# 03_-_MAIN_BOARD.net
KiCad netlist of a schematic drawn in Altium Designer
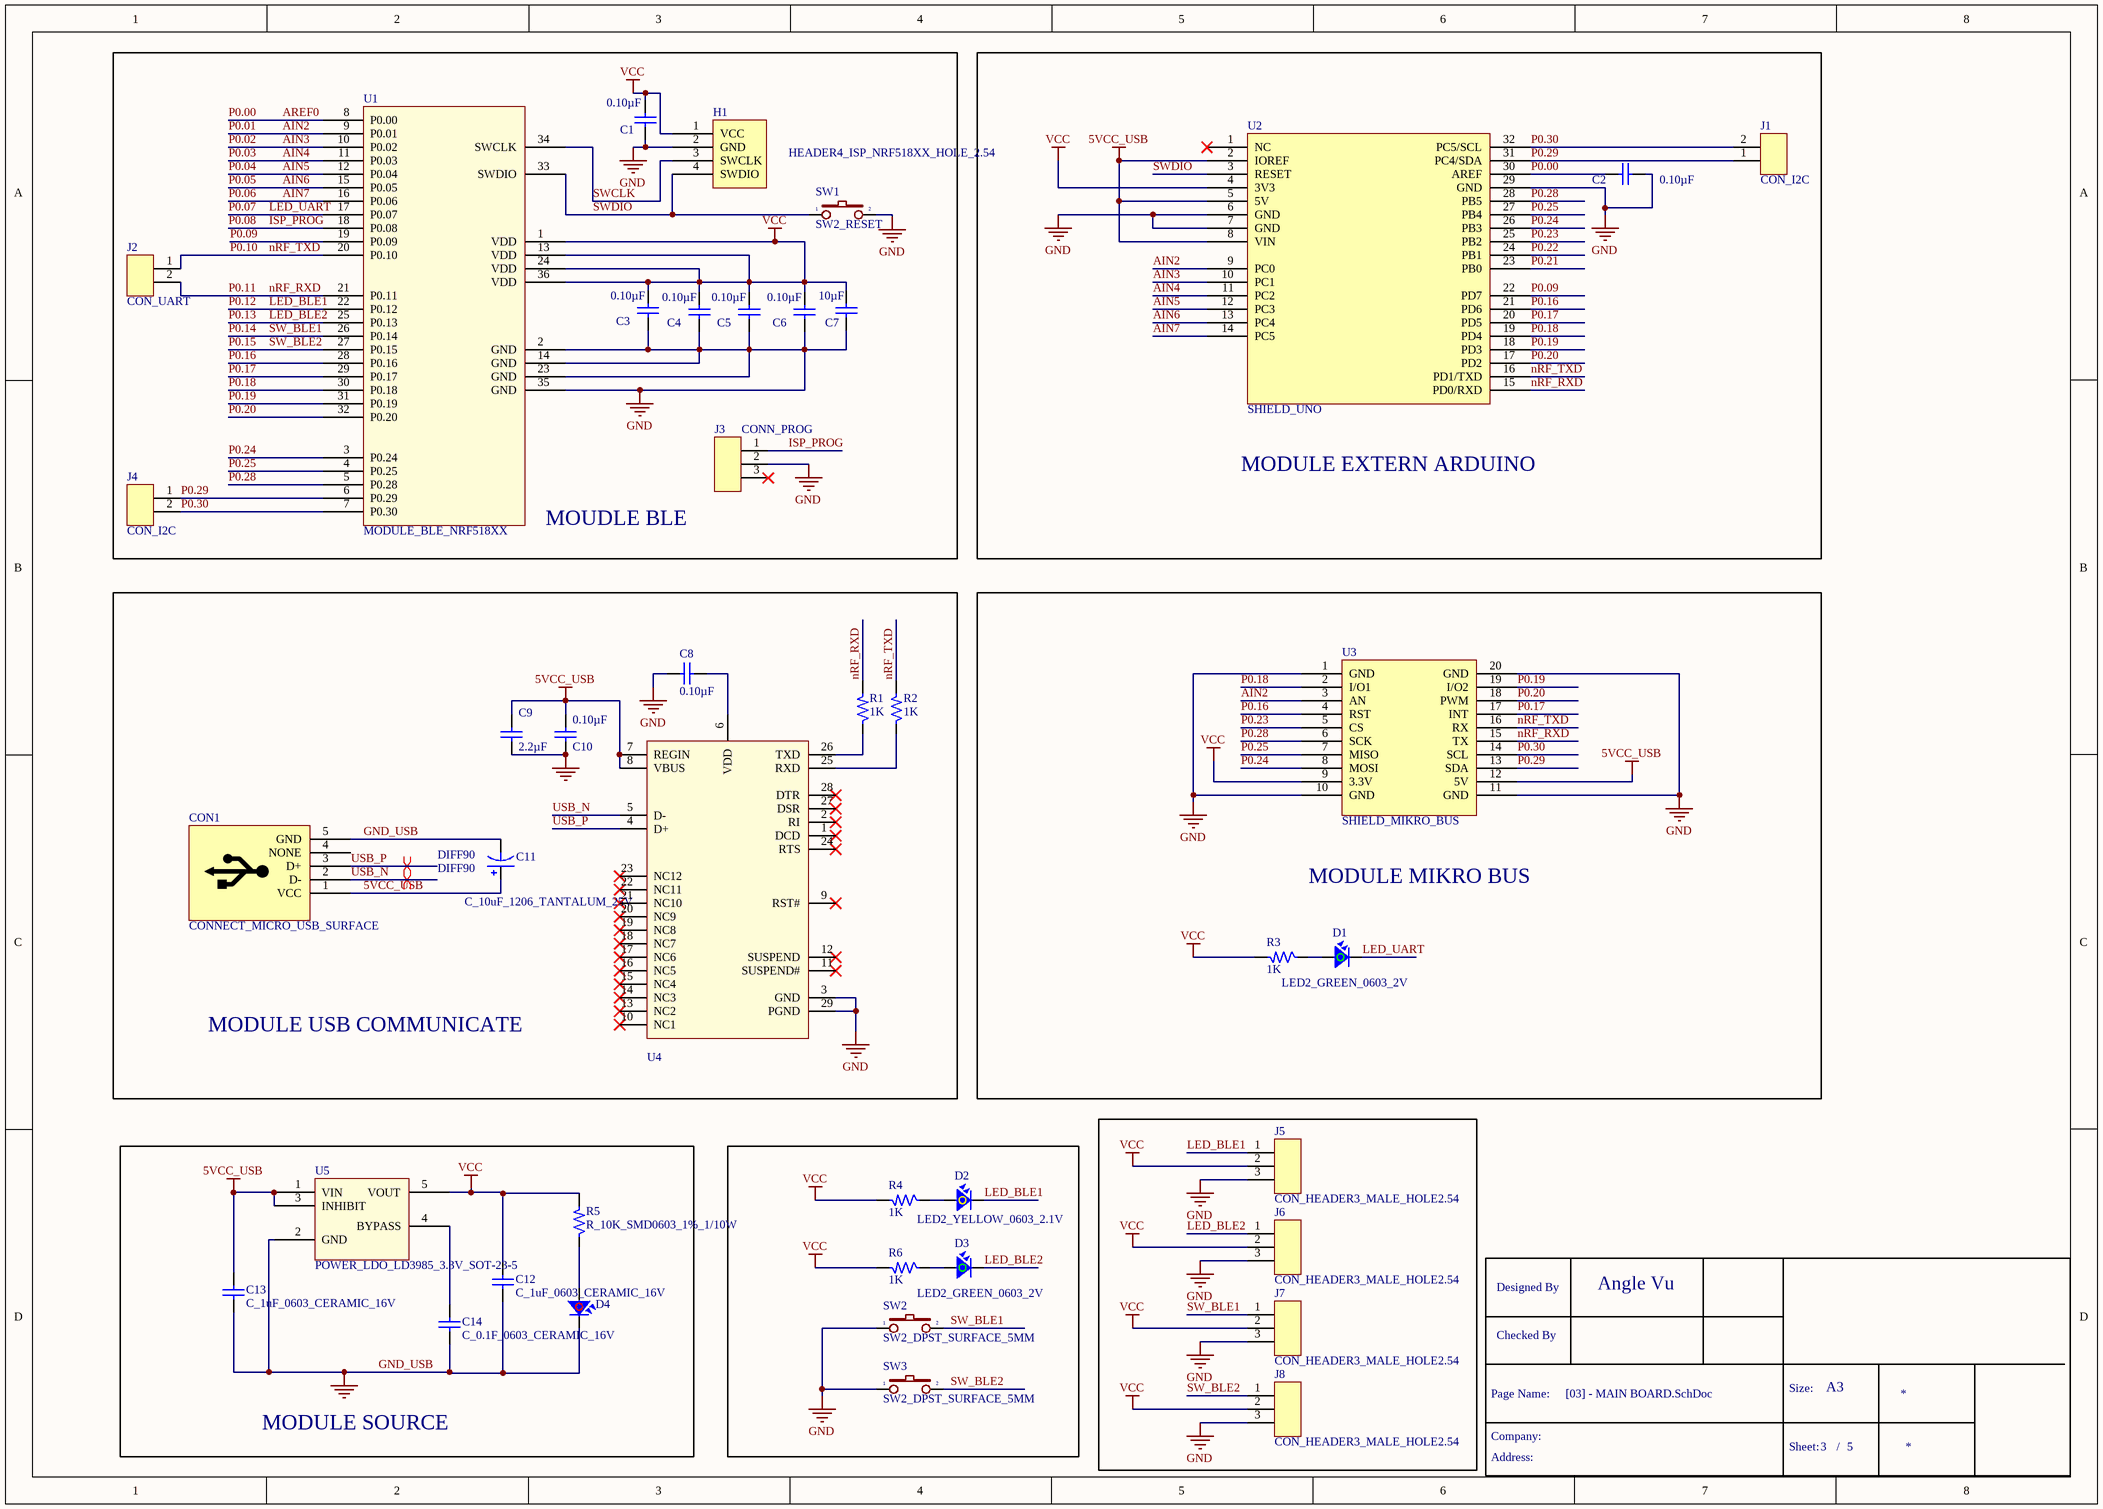
[diagram p0: [03] - MAIN BOARD.SchDoc]

(export (version "E")
  (design (tool "Eeschema 10.0.6"))
  (components
    (comp (ref "C1")
      (value "C_0.1F_0603_CERAMIC_16V")
      (footprint "CAP_SMD0603")
      (description "CAP CER 0.1UF 16V X7R 0603")
      (fields
        (field (name "MANUFACTURER") "Murata Electronics North America")
        (field (name "MANUFACTURER PART NUMBER") "GRM188R71C104KA01D")
        (field (name "CAPACITANCE") "0.10µF")
      )
      (libsource (lib "LIB_ALTIUM") (part "C_0.1F_0603_CERAMIC_16V"))
    )
    (comp (ref "C2")
      (value "C_0.1F_0603_CERAMIC_16V")
      (footprint "CAP_SMD0603")
      (description "CAP CER 0.1UF 16V X7R 0603")
      (fields
        (field (name "MANUFACTURER") "Murata Electronics North America")
        (field (name "MANUFACTURER PART NUMBER") "GRM188R71C104KA01D")
        (field (name "CAPACITANCE") "0.10µF")
      )
      (libsource (lib "LIB_ALTIUM") (part "C_0.1F_0603_CERAMIC_16V"))
    )
    (comp (ref "C3")
      (value "C_0.1F_0603_CERAMIC_16V")
      (footprint "CAP_SMD0603")
      (description "CAP CER 0.1UF 16V X7R 0603")
      (fields
        (field (name "MANUFACTURER") "Murata Electronics North America")
        (field (name "MANUFACTURER PART NUMBER") "GRM188R71C104KA01D")
        (field (name "CAPACITANCE") "0.10µF")
      )
      (libsource (lib "LIB_ALTIUM") (part "C_0.1F_0603_CERAMIC_16V"))
    )
    (comp (ref "C4")
      (value "C_0.1F_0603_CERAMIC_16V")
      (footprint "CAP_SMD0603")
      (description "CAP CER 0.1UF 16V X7R 0603")
      (fields
        (field (name "MANUFACTURER") "Murata Electronics North America")
        (field (name "MANUFACTURER PART NUMBER") "GRM188R71C104KA01D")
        (field (name "CAPACITANCE") "0.10µF")
      )
      (libsource (lib "LIB_ALTIUM") (part "C_0.1F_0603_CERAMIC_16V"))
    )
    (comp (ref "C5")
      (value "C_0.1F_0603_CERAMIC_16V")
      (footprint "CAP_SMD0603")
      (description "CAP CER 0.1UF 16V X7R 0603")
      (fields
        (field (name "MANUFACTURER") "Murata Electronics North America")
        (field (name "MANUFACTURER PART NUMBER") "GRM188R71C104KA01D")
        (field (name "CAPACITANCE") "0.10µF")
      )
      (libsource (lib "LIB_ALTIUM") (part "C_0.1F_0603_CERAMIC_16V"))
    )
    (comp (ref "C6")
      (value "C_0.1F_0603_CERAMIC_16V")
      (footprint "CAP_SMD0603")
      (description "CAP CER 0.1UF 16V X7R 0603")
      (fields
        (field (name "MANUFACTURER") "Murata Electronics North America")
        (field (name "MANUFACTURER PART NUMBER") "GRM188R71C104KA01D")
        (field (name "CAPACITANCE") "0.10µF")
      )
      (libsource (lib "LIB_ALTIUM") (part "C_0.1F_0603_CERAMIC_16V"))
    )
    (comp (ref "C7")
      (value "C_10uF_0603_CERAMIC_16V")
      (footprint "CAP_SMD0603")
      (description "CAP CER 10UF 16V X5R 0603")
      (fields
        (field (name "MANUFACTURER") "Murata Electronics North America")
        (field (name "MANUFACTURER PART NUMBER") "GRM188R61C106KAALD")
        (field (name "CAPACITANCE") "10µF")
      )
      (libsource (lib "LIB_ALTIUM") (part "C_10uF_0603_CERAMIC_16V"))
    )
    (comp (ref "C8")
      (value "C_0.1F_0603_CERAMIC_16V")
      (footprint "CAP_SMD0603")
      (description "CAP CER 0.1UF 16V X7R 0603")
      (fields
        (field (name "MANUFACTURER") "Murata Electronics North America")
        (field (name "MANUFACTURER PART NUMBER") "GRM188R71C104KA01D")
        (field (name "CAPACITANCE") "0.10µF")
      )
      (libsource (lib "LIB_ALTIUM") (part "C_0.1F_0603_CERAMIC_16V"))
    )
    (comp (ref "C9")
      (value "C_2.2uF_0603_CERAMIC_16V")
      (footprint "CAP_SMD0603")
      (description "CAP CER 2.2UF 16V X5R 0603")
      (fields
        (field (name "MANUFACTURER") "Murata Electronics North America")
        (field (name "MANUFACTURER PART NUMBER") "GRM188R61C225KE15D")
        (field (name "CAPACITANCE") "2.2µF")
      )
      (libsource (lib "LIB_ALTIUM") (part "C_2.2uF_0603_CERAMIC_16V"))
    )
    (comp (ref "C10")
      (value "C_0.1F_0603_CERAMIC_16V")
      (footprint "CAP_SMD0603")
      (description "CAP CER 0.1UF 16V X7R 0603")
      (fields
        (field (name "MANUFACTURER") "Murata Electronics North America")
        (field (name "MANUFACTURER PART NUMBER") "GRM188R71C104KA01D")
        (field (name "CAPACITANCE") "0.10µF")
      )
      (libsource (lib "LIB_ALTIUM") (part "C_0.1F_0603_CERAMIC_16V"))
    )
    (comp (ref "C11")
      (value "C_10uF_1206_TANTALUM_25V")
      (footprint "CAP_SMD1206_TANTALUM")
      (description "CAP TANT 10UF 25V 10% 1206")
      (fields
        (field (name "MANUFACTURER") "AVX Corporation")
        (field (name "MANUFACTURER PART NUMBER") "F951E106KAAAQ2")
      )
      (libsource (lib "LIB_ALTIUM") (part "C_10uF_1206_TANTALUM_25V"))
    )
    (comp (ref "C12")
      (value "C_1uF_0603_CERAMIC_16V")
      (footprint "CAP_SMD0603")
      (description "CAP CER 1UF 16V X5R 0603")
      (fields
        (field (name "MANUFACTURER") "Murata Electronics North America")
        (field (name "MANUFACTURER PART NUMBER") "GRM188R61C105KA93D")
      )
      (libsource (lib "LIB_ALTIUM") (part "C_1uF_0603_CERAMIC_16V"))
    )
    (comp (ref "C13")
      (value "C_1uF_0603_CERAMIC_16V")
      (footprint "CAP_SMD0603")
      (description "CAP CER 1UF 16V X5R 0603")
      (fields
        (field (name "MANUFACTURER") "Murata Electronics North America")
        (field (name "MANUFACTURER PART NUMBER") "GRM188R61C105KA93D")
      )
      (libsource (lib "LIB_ALTIUM") (part "C_1uF_0603_CERAMIC_16V"))
    )
    (comp (ref "C14")
      (value "C_0.1F_0603_CERAMIC_16V")
      (footprint "CAP_SMD0603")
      (description "CAP CER 0.1UF 16V X7R 0603")
      (fields
        (field (name "MANUFACTURER") "Murata Electronics North America")
        (field (name "MANUFACTURER PART NUMBER") "GRM188R71C104KA01D")
      )
      (libsource (lib "LIB_ALTIUM") (part "C_0.1F_0603_CERAMIC_16V"))
    )
    (comp (ref "CON1")
      (value "CONNECT_MICRO_USB_SURFACE")
      (footprint "CON_MICRO_USB_HOLE")
      (description "CONN RCPT STD MICRO USB TYPE B")
      (fields
        (field (name "MANUFACTURER") "Amphenol FCI")
        (field (name "MANUFACTURER PART NUMBER") "10103593-0001LF")
      )
      (libsource (lib "LIB_ALTIUM") (part "CONNECT_MICRO_USB_SURFACE"))
    )
    (comp (ref "D1")
      (value "LED2_GREEN_0603_2V")
      (footprint "LED_GREEN_SMD0603")
      (description "LED GREEN CLEAR 0603 SMD")
      (fields
        (field (name "MANUFACTURER") "Lite-On Inc.")
        (field (name "MANUFACTURER PART NUMBER") "LTST-C191KGKT")
      )
      (libsource (lib "LIB_ALTIUM") (part "LED2_GREEN_0603_2V"))
    )
    (comp (ref "D2")
      (value "LED2_YELLOW_0603_2.1V")
      (footprint "LED_YELLOW_SMD0603")
      (description "LED YELLOW CLEAR 0603 SMD")
      (fields
        (field (name "MANUFACTURER") "Lite-On Inc.")
        (field (name "MANUFACTURER PART NUMBER") "LTST-C191KSKT")
      )
      (libsource (lib "LIB_ALTIUM") (part "LED2_YELLOW_0603_2.1V"))
    )
    (comp (ref "D3")
      (value "LED2_GREEN_0603_2V")
      (footprint "LED_GREEN_SMD0603")
      (description "LED GREEN CLEAR 0603 SMD")
      (fields
        (field (name "MANUFACTURER") "Lite-On Inc.")
        (field (name "MANUFACTURER PART NUMBER") "LTST-C191KGKT")
      )
      (libsource (lib "LIB_ALTIUM") (part "LED2_GREEN_0603_2V"))
    )
    (comp (ref "D4")
      (value "LED2_RED_0603_2V")
      (footprint "LED_RED_SMD0603")
      (description "LED RED CLEAR 0603 SMD")
      (fields
        (field (name "MANUFACTURER") "Lite-On Inc.")
        (field (name "MANUFACTURER PART NUMBER") "LTST-C191KRKT")
      )
      (libsource (lib "LIB_ALTIUM") (part "LED2_RED_0603_2V"))
    )
    (comp (ref "H1")
      (value "HEADER4_ISP_NRF518XX_HOLE_2.54")
      (footprint "HEADER4_ISP_HOLE_2.54")
      (description "CONN HEADER 4POS .100 STR TIN")
      (fields
        (field (name "MANUFACTURER") "Amphenol FCI")
        (field (name "MANUFACTURER PART NUMBER") "68002-404HLF")
      )
      (libsource (lib "LIB_ALTIUM") (part "HEADER4_ISP_NRF518XX_HOLE_2.54"))
    )
    (comp (ref "J1")
      (value "CON_I2C")
      (footprint "CON_HEADER2_HOLE_2.54")
      (description "CON_HEADER10_HOLE2.54")
      (fields (field (name "MANUFACTURER") "3M") (field (name "MANUFACTURER PART NUMBER") "961102-6404-AR"))
      (libsource (lib "LIB_ALTIUM") (part "CON_HEADER2_MALE_HOLE2.54"))
    )
    (comp (ref "J2")
      (value "CON_UART")
      (footprint "CON_HEADER2_HOLE_2.54")
      (description "CON_HEADER10_HOLE2.54")
      (fields (field (name "MANUFACTURER") "3M") (field (name "MANUFACTURER PART NUMBER") "961102-6404-AR"))
      (libsource (lib "") (part "CON_HEADER2_MALE_HOLE2.54_1"))
    )
    (comp (ref "J3")
      (value "CONN_PROG")
      (footprint "CON_HEADER3_HOLE_2.54")
      (description "CON_HEADER10_HOLE2.54")
      (fields (field (name "MANUFACTURER") "3M") (field (name "MANUFACTURER PART NUMBER") "961102-6404-AR"))
      (libsource (lib "") (part "CON_HEADER3_MALE_HOLE2.54_1"))
    )
    (comp (ref "J4")
      (value "CON_I2C")
      (footprint "CON_HEADER2_HOLE_2.54")
      (description "CON_HEADER10_HOLE2.54")
      (fields (field (name "MANUFACTURER") "3M") (field (name "MANUFACTURER PART NUMBER") "961102-6404-AR"))
      (libsource (lib "") (part "CON_HEADER2_MALE_HOLE2.54_1"))
    )
    (comp (ref "J5")
      (value "CON_HEADER3_MALE_HOLE2.54")
      (footprint "CON_HEADER3_HOLE_2.54")
      (description "CON_HEADER10_HOLE2.54")
      (fields (field (name "MANUFACTURER") "3M") (field (name "MANUFACTURER PART NUMBER") "961102-6404-AR"))
      (libsource (lib "LIB_ALTIUM") (part "CON_HEADER3_MALE_HOLE2.54"))
    )
    (comp (ref "J6")
      (value "CON_HEADER3_MALE_HOLE2.54")
      (footprint "CON_HEADER3_HOLE_2.54")
      (description "CON_HEADER10_HOLE2.54")
      (fields (field (name "MANUFACTURER") "3M") (field (name "MANUFACTURER PART NUMBER") "961102-6404-AR"))
      (libsource (lib "LIB_ALTIUM") (part "CON_HEADER3_MALE_HOLE2.54"))
    )
    (comp (ref "J7")
      (value "CON_HEADER3_MALE_HOLE2.54")
      (footprint "CON_HEADER3_HOLE_2.54")
      (description "CON_HEADER10_HOLE2.54")
      (fields (field (name "MANUFACTURER") "3M") (field (name "MANUFACTURER PART NUMBER") "961102-6404-AR"))
      (libsource (lib "LIB_ALTIUM") (part "CON_HEADER3_MALE_HOLE2.54"))
    )
    (comp (ref "J8")
      (value "CON_HEADER3_MALE_HOLE2.54")
      (footprint "CON_HEADER3_HOLE_2.54")
      (description "CON_HEADER10_HOLE2.54")
      (fields (field (name "MANUFACTURER") "3M") (field (name "MANUFACTURER PART NUMBER") "961102-6404-AR"))
      (libsource (lib "LIB_ALTIUM") (part "CON_HEADER3_MALE_HOLE2.54"))
    )
    (comp (ref "R1")
      (value "R_1K2_SMD0603_1%_1/10W")
      (footprint "RES_SMD0603")
      (description "RES SMD 1.2K OHM 1% 1/10W 0603")
      (fields
        (field (name "MANUFACTURER") "Yageo")
        (field (name "MANUFACTURER PART NUMBER") "RC0603FR-071K2L")
        (field (name "RESISTANCE (OHMS)") "1K")
      )
      (libsource (lib "LIB_ALTIUM") (part "R_1K2_SMD0603_1%_1/10W"))
    )
    (comp (ref "R2")
      (value "R_1K2_SMD0603_1%_1/10W")
      (footprint "RES_SMD0603")
      (description "RES SMD 1.2K OHM 1% 1/10W 0603")
      (fields
        (field (name "MANUFACTURER") "Yageo")
        (field (name "MANUFACTURER PART NUMBER") "RC0603FR-071K2L")
        (field (name "RESISTANCE (OHMS)") "1K")
      )
      (libsource (lib "LIB_ALTIUM") (part "R_1K2_SMD0603_1%_1/10W"))
    )
    (comp (ref "R3")
      (value "R_1K2_SMD0603_1%_1/10W")
      (footprint "RES_SMD0603")
      (description "RES SMD 1.2K OHM 1% 1/10W 0603")
      (fields
        (field (name "MANUFACTURER") "Yageo")
        (field (name "MANUFACTURER PART NUMBER") "RC0603FR-071K2L")
        (field (name "RESISTANCE (OHMS)") "1K")
      )
      (libsource (lib "LIB_ALTIUM") (part "R_1K2_SMD0603_1%_1/10W"))
    )
    (comp (ref "R4")
      (value "R_1K2_SMD0603_1%_1/10W")
      (footprint "RES_SMD0603")
      (description "RES SMD 1.2K OHM 1% 1/10W 0603")
      (fields
        (field (name "MANUFACTURER") "Yageo")
        (field (name "MANUFACTURER PART NUMBER") "RC0603FR-071K2L")
        (field (name "RESISTANCE (OHMS)") "1K")
      )
      (libsource (lib "LIB_ALTIUM") (part "R_1K2_SMD0603_1%_1/10W"))
    )
    (comp (ref "R5")
      (value "R_10K_SMD0603_1%_1/10W")
      (footprint "RES_SMD0603")
      (description "RES SMD 10K OHM 1% 1/10W 0603")
      (fields
        (field (name "MANUFACTURER") "Yageo")
        (field (name "MANUFACTURER PART NUMBER") "RC0603FR-0710KL")
      )
      (libsource (lib "LIB_ALTIUM") (part "R_10K_SMD0603_1%_1/10W"))
    )
    (comp (ref "R6")
      (value "R_1K2_SMD0603_1%_1/10W")
      (footprint "RES_SMD0603")
      (description "RES SMD 1.2K OHM 1% 1/10W 0603")
      (fields
        (field (name "MANUFACTURER") "Yageo")
        (field (name "MANUFACTURER PART NUMBER") "RC0603FR-071K2L")
        (field (name "RESISTANCE (OHMS)") "1K")
      )
      (libsource (lib "LIB_ALTIUM") (part "R_1K2_SMD0603_1%_1/10W"))
    )
    (comp (ref "SW1")
      (value "SW2_RESET")
      (footprint "SW2-SMD")
      (description "SWITCH TACTILE SPST-NO 0.05A 12V")
      (fields
        (field (name "MANUFACTURER") "Wurth Electronics Inc")
        (field (name "MANUFACTURER PART NUMBER") "434121050836")
      )
      (libsource (lib "LIB_ALTIUM") (part "SW2_DPST_SURFACE_5MM"))
    )
    (comp (ref "SW2")
      (value "SW2_DPST_SURFACE_5MM")
      (footprint "SW2-SMD")
      (description "SWITCH TACTILE SPST-NO 0.05A 12V")
      (fields
        (field (name "MANUFACTURER") "Wurth Electronics Inc")
        (field (name "MANUFACTURER PART NUMBER") "434121050836")
      )
      (libsource (lib "LIB_ALTIUM") (part "SW2_DPST_SURFACE_5MM"))
    )
    (comp (ref "SW3")
      (value "SW2_DPST_SURFACE_5MM")
      (footprint "SW2-SMD")
      (description "SWITCH TACTILE SPST-NO 0.05A 12V")
      (fields
        (field (name "MANUFACTURER") "Wurth Electronics Inc")
        (field (name "MANUFACTURER PART NUMBER") "434121050836")
      )
      (libsource (lib "LIB_ALTIUM") (part "SW2_DPST_SURFACE_5MM"))
    )
    (comp (ref "U1")
      (value "MODULE_BLE_NRF518XX")
      (footprint "MODULE_NRF518xx")
      (libsource (lib "LIB_ALTIUM") (part "MODULE_BLE_NRF518XX"))
    )
    (comp (ref "U2")
      (value "SHIELD_UNO")
      (footprint "SHIELD UNO")
      (libsource (lib "LIB_ALTIUM") (part "SHIELD_UNO"))
    )
    (comp (ref "U3")
      (value "SHIELD_MIKRO_BUS")
      (footprint "SHIELD_MIKRO_BUS")
      (libsource (lib "SchematicLib") (part "SHIELD_MIKRO_BUS"))
    )
    (comp (ref "U4")
      (value "USB_CP2102-GMR")
      (footprint "QFN_28PIN_USBC2102")
      (description "IC USB-TO-UART BRIDGE 28VQFN")
      (fields
        (field (name "MANUFACTURER") "Silicon Labs")
        (field (name "MANUFACTURER PART NUMBER") "CP2102-GMR")
      )
      (libsource (lib "LIB_ALTIUM") (part "USB_CP2102-GMR"))
    )
    (comp (ref "U5")
      (value "POWER_LDO_LD3985_3.3V_SOT-23-5")
      (footprint "POWER_LDO_LDR3985-3.3")
      (description "IC REG LDO 3.3V 0.15A SOT23-5")
      (fields
        (field (name "MANUFACTURER") "STMicroelectronics")
        (field (name "MANUFACTURER PART NUMBER") "LD3985M33R")
      )
      (libsource (lib "LIB_ALTIUM") (part "POWER_LDO_LD3985_3.3V_SOT-23-5"))
    )
  )
  (nets
    (net (code "1") (name "/AIN2") (class "Default")
      (node (ref "U1") (pin "9") (pinfunction "P0.01_9") (pintype "passive"))
      (node (ref "U2") (pin "9") (pinfunction "PC0_9") (pintype "passive"))
      (node (ref "U3") (pin "3") (pinfunction "AN_3") (pintype "passive"))
    )
    (net (code "2") (name "/AIN3") (class "Default")
      (node (ref "U1") (pin "10") (pinfunction "P0.02_10") (pintype "passive"))
      (node (ref "U2") (pin "10") (pinfunction "PC1_10") (pintype "passive"))
    )
    (net (code "3") (name "/AIN4") (class "Default")
      (node (ref "U1") (pin "11") (pinfunction "P0.03_11") (pintype "passive"))
      (node (ref "U2") (pin "11") (pinfunction "PC2_11") (pintype "passive"))
    )
    (net (code "4") (name "/AIN5") (class "Default")
      (node (ref "U1") (pin "12") (pinfunction "P0.04_12") (pintype "passive"))
      (node (ref "U2") (pin "12") (pinfunction "PC3_12") (pintype "passive"))
    )
    (net (code "5") (name "/AIN6") (class "Default")
      (node (ref "U1") (pin "15") (pinfunction "P0.05_15") (pintype "passive"))
      (node (ref "U2") (pin "13") (pinfunction "PC4_13") (pintype "passive"))
    )
    (net (code "6") (name "/AIN7") (class "Default")
      (node (ref "U1") (pin "16") (pinfunction "P0.06_16") (pintype "passive"))
      (node (ref "U2") (pin "14") (pinfunction "PC5_14") (pintype "passive"))
    )
    (net (code "7") (name "/AREF0") (class "Default")
      (node (ref "C2") (pin "1") (pinfunction "1_1") (pintype "passive"))
      (node (ref "U1") (pin "8") (pinfunction "P0.00_8") (pintype "passive"))
      (node (ref "U2") (pin "30") (pinfunction "AREF_30") (pintype "passive"))
    )
    (net (code "8") (name "/ISP_PROG") (class "Default")
      (node (ref "J3") (pin "1") (pinfunction "SIGN+_1") (pintype "passive"))
      (node (ref "U1") (pin "18") (pinfunction "P0.08_18") (pintype "passive"))
    )
    (net (code "9") (name "/LED_BLE1") (class "Default")
      (node (ref "D2") (pin "2") (pinfunction "2_2") (pintype "passive"))
      (node (ref "J5") (pin "1") (pinfunction "SIGN+_1") (pintype "passive"))
      (node (ref "U1") (pin "22") (pinfunction "P0.12_22") (pintype "passive"))
    )
    (net (code "10") (name "/LED_BLE2") (class "Default")
      (node (ref "D3") (pin "2") (pinfunction "2_2") (pintype "passive"))
      (node (ref "J6") (pin "1") (pinfunction "SIGN+_1") (pintype "passive"))
      (node (ref "U1") (pin "25") (pinfunction "P0.13_25") (pintype "passive"))
    )
    (net (code "11") (name "/LED_UART") (class "Default")
      (node (ref "D1") (pin "2") (pinfunction "2_2") (pintype "passive"))
      (node (ref "U1") (pin "17") (pinfunction "P0.07_17") (pintype "passive"))
    )
    (net (code "12") (name "/P0.09") (class "Default")
      (node (ref "U1") (pin "19") (pinfunction "P0.09_19") (pintype "passive"))
      (node (ref "U2") (pin "22") (pinfunction "PD7_22") (pintype "passive"))
    )
    (net (code "13") (name "/P0.10") (class "Default")
      (node (ref "J2") (pin "1") (pinfunction "SIGN+_1") (pintype "passive"))
      (node (ref "R2") (pin "2") (pinfunction "2_2") (pintype "passive"))
      (node (ref "U1") (pin "20") (pinfunction "P0.10_20") (pintype "passive"))
      (node (ref "U2") (pin "16") (pinfunction "PD1/TXD_16") (pintype "passive"))
      (node (ref "U3") (pin "16") (pinfunction "RX_16") (pintype "passive"))
    )
    (net (code "14") (name "/P0.11") (class "Default")
      (node (ref "J2") (pin "2") (pinfunction "SIGN-_2") (pintype "passive"))
      (node (ref "R1") (pin "2") (pinfunction "2_2") (pintype "passive"))
      (node (ref "U1") (pin "21") (pinfunction "P0.11_21") (pintype "passive"))
      (node (ref "U2") (pin "15") (pinfunction "PD0/RXD_15") (pintype "passive"))
      (node (ref "U3") (pin "15") (pinfunction "TX_15") (pintype "passive"))
    )
    (net (code "15") (name "/P0.14") (class "Default")
      (node (ref "J7") (pin "1") (pinfunction "SIGN+_1") (pintype "passive"))
      (node (ref "SW2") (pin "2") (pinfunction "2_2") (pintype "passive"))
      (node (ref "U1") (pin "26") (pinfunction "P0.14_26") (pintype "passive"))
    )
    (net (code "16") (name "/P0.15") (class "Default")
      (node (ref "J8") (pin "1") (pinfunction "SIGN+_1") (pintype "passive"))
      (node (ref "SW3") (pin "2") (pinfunction "2_2") (pintype "passive"))
      (node (ref "U1") (pin "27") (pinfunction "P0.15_27") (pintype "passive"))
    )
    (net (code "17") (name "/P0.16") (class "Default")
      (node (ref "U1") (pin "28") (pinfunction "P0.16_28") (pintype "passive"))
      (node (ref "U2") (pin "21") (pinfunction "PD6_21") (pintype "passive"))
      (node (ref "U3") (pin "4") (pinfunction "RST_4") (pintype "passive"))
    )
    (net (code "18") (name "/P0.17") (class "Default")
      (node (ref "U1") (pin "29") (pinfunction "P0.17_29") (pintype "passive"))
      (node (ref "U2") (pin "20") (pinfunction "PD5_20") (pintype "passive"))
      (node (ref "U3") (pin "17") (pinfunction "INT_17") (pintype "passive"))
    )
    (net (code "19") (name "/P0.18") (class "Default")
      (node (ref "U1") (pin "30") (pinfunction "P0.18_30") (pintype "passive"))
      (node (ref "U2") (pin "19") (pinfunction "PD4_19") (pintype "passive"))
      (node (ref "U3") (pin "2") (pinfunction "I/O1_2") (pintype "passive"))
    )
    (net (code "20") (name "/P0.19") (class "Default")
      (node (ref "U1") (pin "31") (pinfunction "P0.19_31") (pintype "passive"))
      (node (ref "U2") (pin "18") (pinfunction "PD3_18") (pintype "passive"))
      (node (ref "U3") (pin "19") (pinfunction "I/O2_19") (pintype "passive"))
    )
    (net (code "21") (name "/P0.20") (class "Default")
      (node (ref "U1") (pin "32") (pinfunction "P0.20_32") (pintype "passive"))
      (node (ref "U2") (pin "17") (pinfunction "PD2_17") (pintype "passive"))
      (node (ref "U3") (pin "18") (pinfunction "PWM_18") (pintype "passive"))
    )
    (net (code "22") (name "/P0.21") (class "Default")
      (node (ref "U2") (pin "23") (pinfunction "PB0_23") (pintype "passive"))
    )
    (net (code "23") (name "/P0.22") (class "Default")
      (node (ref "U2") (pin "24") (pinfunction "PB1_24") (pintype "passive"))
    )
    (net (code "24") (name "/P0.23") (class "Default")
      (node (ref "U2") (pin "25") (pinfunction "PB2_25") (pintype "passive"))
      (node (ref "U3") (pin "5") (pinfunction "CS_5") (pintype "passive"))
    )
    (net (code "25") (name "/P0.24") (class "Default")
      (node (ref "U1") (pin "3") (pinfunction "P0.24_3") (pintype "passive"))
      (node (ref "U2") (pin "26") (pinfunction "PB3_26") (pintype "passive"))
      (node (ref "U3") (pin "8") (pinfunction "MOSI_8") (pintype "passive"))
    )
    (net (code "26") (name "/P0.25") (class "Default")
      (node (ref "U1") (pin "4") (pinfunction "P0.25_4") (pintype "passive"))
      (node (ref "U2") (pin "27") (pinfunction "PB4_27") (pintype "passive"))
      (node (ref "U3") (pin "7") (pinfunction "MISO_7") (pintype "passive"))
    )
    (net (code "27") (name "/P0.28") (class "Default")
      (node (ref "U1") (pin "5") (pinfunction "P0.28_5") (pintype "passive"))
      (node (ref "U2") (pin "28") (pinfunction "PB5_28") (pintype "passive"))
      (node (ref "U3") (pin "6") (pinfunction "SCK_6") (pintype "passive"))
    )
    (net (code "28") (name "/P0.29") (class "Default")
      (node (ref "J1") (pin "1") (pinfunction "SIGN+_1") (pintype "passive"))
      (node (ref "J4") (pin "1") (pinfunction "SIGN+_1") (pintype "passive"))
      (node (ref "U1") (pin "6") (pinfunction "P0.29_6") (pintype "passive"))
      (node (ref "U2") (pin "31") (pinfunction "PC4/SDA_31") (pintype "passive"))
      (node (ref "U3") (pin "13") (pinfunction "SDA_13") (pintype "passive"))
    )
    (net (code "29") (name "/P0.30") (class "Default")
      (node (ref "J1") (pin "2") (pinfunction "SIGN-_2") (pintype "passive"))
      (node (ref "J4") (pin "2") (pinfunction "SIGN-_2") (pintype "passive"))
      (node (ref "U1") (pin "7") (pinfunction "P0.30_7") (pintype "passive"))
      (node (ref "U2") (pin "32") (pinfunction "PC5/SCL_32") (pintype "passive"))
      (node (ref "U3") (pin "14") (pinfunction "SCL_14") (pintype "passive"))
    )
    (net (code "30") (name "/SWCLK") (class "Default")
      (node (ref "H1") (pin "3") (pinfunction "SWCLK_3") (pintype "passive"))
      (node (ref "U1") (pin "34") (pinfunction "SWCLK_34") (pintype "passive"))
    )
    (net (code "31") (name "/SWDIO") (class "Default")
      (node (ref "H1") (pin "4") (pinfunction "SWDIO_4") (pintype "passive"))
      (node (ref "SW1") (pin "1") (pinfunction "1_1") (pintype "passive"))
      (node (ref "U1") (pin "33") (pinfunction "SWDIO_33") (pintype "passive"))
      (node (ref "U2") (pin "3") (pinfunction "RESET_3") (pintype "passive"))
    )
    (net (code "32") (name "/USB_N") (class "Default")
      (node (ref "CON1") (pin "2") (pinfunction "D-_2") (pintype "passive"))
      (node (ref "U4") (pin "5") (pinfunction "D-_5") (pintype "passive"))
    )
    (net (code "33") (name "/USB_P") (class "Default")
      (node (ref "CON1") (pin "3") (pinfunction "D+_3") (pintype "passive"))
      (node (ref "U4") (pin "4") (pinfunction "D+_4") (pintype "passive"))
    )
    (net (code "34") (name "5VCC_USB") (class "Default")
      (node (ref "C10") (pin "2") (pinfunction "2_2") (pintype "passive"))
      (node (ref "C11") (pin "1") (pinfunction "1_1") (pintype "passive"))
      (node (ref "C13") (pin "2") (pinfunction "2_2") (pintype "passive"))
      (node (ref "C9") (pin "2") (pinfunction "2_2") (pintype "passive"))
      (node (ref "CON1") (pin "1") (pinfunction "VCC_1") (pintype "passive"))
      (node (ref "U2") (pin "2") (pinfunction "IOREF_2") (pintype "passive"))
      (node (ref "U2") (pin "5") (pinfunction "5V_5") (pintype "passive"))
      (node (ref "U2") (pin "8") (pinfunction "VIN_8") (pintype "passive"))
      (node (ref "U3") (pin "12") (pinfunction "5V_12") (pintype "passive"))
      (node (ref "U4") (pin "7") (pinfunction "REGIN_7") (pintype "passive"))
      (node (ref "U4") (pin "8") (pinfunction "VBUS_8") (pintype "passive"))
      (node (ref "U5") (pin "1") (pinfunction "VIN_1") (pintype "passive"))
      (node (ref "U5") (pin "3") (pinfunction "INHIBIT_3") (pintype "passive"))
    )
    (net (code "35") (name "GND") (class "Default")
      (node (ref "C1") (pin "1") (pinfunction "1_1") (pintype "passive"))
      (node (ref "C10") (pin "1") (pinfunction "1_1") (pintype "passive"))
      (node (ref "C11") (pin "2") (pinfunction "2_2") (pintype "passive"))
      (node (ref "C12") (pin "1") (pinfunction "1_1") (pintype "passive"))
      (node (ref "C13") (pin "1") (pinfunction "1_1") (pintype "passive"))
      (node (ref "C14") (pin "1") (pinfunction "1_1") (pintype "passive"))
      (node (ref "C2") (pin "2") (pinfunction "2_2") (pintype "passive"))
      (node (ref "C3") (pin "1") (pinfunction "1_1") (pintype "passive"))
      (node (ref "C4") (pin "1") (pinfunction "1_1") (pintype "passive"))
      (node (ref "C5") (pin "1") (pinfunction "1_1") (pintype "passive"))
      (node (ref "C6") (pin "1") (pinfunction "1_1") (pintype "passive"))
      (node (ref "C7") (pin "1") (pinfunction "1_1") (pintype "passive"))
      (node (ref "C8") (pin "2") (pinfunction "2_2") (pintype "passive"))
      (node (ref "C9") (pin "1") (pinfunction "1_1") (pintype "passive"))
      (node (ref "CON1") (pin "5") (pinfunction "GND_5") (pintype "passive"))
      (node (ref "D4") (pin "2") (pinfunction "2_2") (pintype "passive"))
      (node (ref "H1") (pin "2") (pinfunction "GND_2") (pintype "passive"))
      (node (ref "J3") (pin "2") (pinfunction "SIGN-_2") (pintype "passive"))
      (node (ref "J5") (pin "3") (pinfunction "3_3") (pintype "passive"))
      (node (ref "J6") (pin "3") (pinfunction "3_3") (pintype "passive"))
      (node (ref "J7") (pin "3") (pinfunction "3_3") (pintype "passive"))
      (node (ref "J8") (pin "3") (pinfunction "3_3") (pintype "passive"))
      (node (ref "SW1") (pin "2") (pinfunction "2_2") (pintype "passive"))
      (node (ref "SW2") (pin "1") (pinfunction "1_1") (pintype "passive"))
      (node (ref "SW3") (pin "1") (pinfunction "1_1") (pintype "passive"))
      (node (ref "U1") (pin "14") (pinfunction "GND_14") (pintype "passive"))
      (node (ref "U1") (pin "2") (pinfunction "GND_2") (pintype "passive"))
      (node (ref "U1") (pin "23") (pinfunction "GND_23") (pintype "passive"))
      (node (ref "U1") (pin "35") (pinfunction "GND_35") (pintype "passive"))
      (node (ref "U2") (pin "29") (pinfunction "GND_29") (pintype "passive"))
      (node (ref "U2") (pin "6") (pinfunction "GND_6") (pintype "passive"))
      (node (ref "U2") (pin "7") (pinfunction "GND_7") (pintype "passive"))
      (node (ref "U3") (pin "1") (pinfunction "GND_1") (pintype "passive"))
      (node (ref "U3") (pin "10") (pinfunction "GND_10") (pintype "passive"))
      (node (ref "U3") (pin "11") (pinfunction "GND_11") (pintype "passive"))
      (node (ref "U3") (pin "20") (pinfunction "GND_20") (pintype "passive"))
      (node (ref "U4") (pin "29") (pinfunction "PGND_29") (pintype "passive"))
      (node (ref "U4") (pin "3") (pinfunction "GND_3") (pintype "passive"))
      (node (ref "U5") (pin "2") (pinfunction "GND_2") (pintype "passive"))
    )
    (net (code "36") (name "Net-(D1-Pad1)") (class "Default")
      (node (ref "D1") (pin "1") (pinfunction "1_1") (pintype "passive"))
      (node (ref "R3") (pin "1") (pinfunction "1_1") (pintype "passive"))
    )
    (net (code "37") (name "Net-(D2-Pad1)") (class "Default")
      (node (ref "D2") (pin "1") (pinfunction "1_1") (pintype "passive"))
      (node (ref "R4") (pin "1") (pinfunction "1_1") (pintype "passive"))
    )
    (net (code "38") (name "Net-(D3-Pad1)") (class "Default")
      (node (ref "D3") (pin "1") (pinfunction "1_1") (pintype "passive"))
      (node (ref "R6") (pin "1") (pinfunction "1_1") (pintype "passive"))
    )
    (net (code "39") (name "Net-(D4-Pad1)") (class "Default")
      (node (ref "D4") (pin "1") (pinfunction "1_1") (pintype "passive"))
      (node (ref "R5") (pin "1") (pinfunction "1_1") (pintype "passive"))
    )
    (net (code "40") (name "Net-(U4-RXD)") (class "Default")
      (node (ref "R2") (pin "1") (pinfunction "1_1") (pintype "passive"))
      (node (ref "U4") (pin "25") (pinfunction "RXD_25") (pintype "passive"))
    )
    (net (code "41") (name "Net-(U4-TXD)") (class "Default")
      (node (ref "R1") (pin "1") (pinfunction "1_1") (pintype "passive"))
      (node (ref "U4") (pin "26") (pinfunction "TXD_26") (pintype "passive"))
    )
    (net (code "42") (name "Net-(U4-VDD)") (class "Default")
      (node (ref "C8") (pin "1") (pinfunction "1_1") (pintype "passive"))
      (node (ref "U4") (pin "6") (pinfunction "VDD_6") (pintype "passive"))
    )
    (net (code "43") (name "Net-(U5-BYPASS)") (class "Default")
      (node (ref "C14") (pin "2") (pinfunction "2_2") (pintype "passive"))
      (node (ref "U5") (pin "4") (pinfunction "BYPASS_4") (pintype "passive"))
    )
    (net (code "44") (name "VCC") (class "Default")
      (node (ref "C1") (pin "2") (pinfunction "2_2") (pintype "passive"))
      (node (ref "C12") (pin "2") (pinfunction "2_2") (pintype "passive"))
      (node (ref "C3") (pin "2") (pinfunction "2_2") (pintype "passive"))
      (node (ref "C4") (pin "2") (pinfunction "2_2") (pintype "passive"))
      (node (ref "C5") (pin "2") (pinfunction "2_2") (pintype "passive"))
      (node (ref "C6") (pin "2") (pinfunction "2_2") (pintype "passive"))
      (node (ref "C7") (pin "2") (pinfunction "2_2") (pintype "passive"))
      (node (ref "H1") (pin "1") (pinfunction "VCC_1") (pintype "passive"))
      (node (ref "J5") (pin "2") (pinfunction "SIGN-_2") (pintype "passive"))
      (node (ref "J6") (pin "2") (pinfunction "SIGN-_2") (pintype "passive"))
      (node (ref "J7") (pin "2") (pinfunction "SIGN-_2") (pintype "passive"))
      (node (ref "J8") (pin "2") (pinfunction "SIGN-_2") (pintype "passive"))
      (node (ref "R3") (pin "2") (pinfunction "2_2") (pintype "passive"))
      (node (ref "R4") (pin "2") (pinfunction "2_2") (pintype "passive"))
      (node (ref "R5") (pin "2") (pinfunction "2_2") (pintype "passive"))
      (node (ref "R6") (pin "2") (pinfunction "2_2") (pintype "passive"))
      (node (ref "U1") (pin "1") (pinfunction "VDD_1") (pintype "passive"))
      (node (ref "U1") (pin "13") (pinfunction "VDD_13") (pintype "passive"))
      (node (ref "U1") (pin "24") (pinfunction "VDD_24") (pintype "passive"))
      (node (ref "U1") (pin "36") (pinfunction "VDD_36") (pintype "passive"))
      (node (ref "U2") (pin "4") (pinfunction "3V3_4") (pintype "passive"))
      (node (ref "U3") (pin "9") (pinfunction "3.3V_9") (pintype "passive"))
      (node (ref "U5") (pin "5") (pinfunction "VOUT_5") (pintype "passive"))
    )
    (net (code "45") (name "unconnected-(CON1-NONE-Pad4)") (class "Default")
      (node (ref "CON1") (pin "4") (pinfunction "NONE_4") (pintype "passive"))
    )
    (net (code "46") (name "unconnected-(J3-Pad3)") (class "Default")
      (node (ref "J3") (pin "3") (pinfunction "3_3") (pintype "passive+no_connect"))
    )
    (net (code "47") (name "unconnected-(U2-NC-Pad1)") (class "Default")
      (node (ref "U2") (pin "1") (pinfunction "NC_1") (pintype "passive+no_connect"))
    )
    (net (code "48") (name "unconnected-(U4-DCD-Pad1)") (class "Default")
      (node (ref "U4") (pin "1") (pinfunction "DCD_1") (pintype "passive+no_connect"))
    )
    (net (code "49") (name "unconnected-(U4-DSR-Pad27)") (class "Default")
      (node (ref "U4") (pin "27") (pinfunction "DSR_27") (pintype "passive+no_connect"))
    )
    (net (code "50") (name "unconnected-(U4-DTR-Pad28)") (class "Default")
      (node (ref "U4") (pin "28") (pinfunction "DTR_28") (pintype "passive+no_connect"))
    )
    (net (code "51") (name "unconnected-(U4-NC1-Pad10)") (class "Default")
      (node (ref "U4") (pin "10") (pinfunction "NC1_10") (pintype "passive+no_connect"))
    )
    (net (code "52") (name "unconnected-(U4-NC2-Pad13)") (class "Default")
      (node (ref "U4") (pin "13") (pinfunction "NC2_13") (pintype "passive+no_connect"))
    )
    (net (code "53") (name "unconnected-(U4-NC3-Pad14)") (class "Default")
      (node (ref "U4") (pin "14") (pinfunction "NC3_14") (pintype "passive+no_connect"))
    )
    (net (code "54") (name "unconnected-(U4-NC4-Pad15)") (class "Default")
      (node (ref "U4") (pin "15") (pinfunction "NC4_15") (pintype "passive+no_connect"))
    )
    (net (code "55") (name "unconnected-(U4-NC5-Pad16)") (class "Default")
      (node (ref "U4") (pin "16") (pinfunction "NC5_16") (pintype "passive+no_connect"))
    )
    (net (code "56") (name "unconnected-(U4-NC6-Pad17)") (class "Default")
      (node (ref "U4") (pin "17") (pinfunction "NC6_17") (pintype "passive+no_connect"))
    )
    (net (code "57") (name "unconnected-(U4-NC7-Pad18)") (class "Default")
      (node (ref "U4") (pin "18") (pinfunction "NC7_18") (pintype "passive+no_connect"))
    )
    (net (code "58") (name "unconnected-(U4-NC8-Pad19)") (class "Default")
      (node (ref "U4") (pin "19") (pinfunction "NC8_19") (pintype "passive+no_connect"))
    )
    (net (code "59") (name "unconnected-(U4-NC9-Pad20)") (class "Default")
      (node (ref "U4") (pin "20") (pinfunction "NC9_20") (pintype "passive+no_connect"))
    )
    (net (code "60") (name "unconnected-(U4-NC10-Pad21)") (class "Default")
      (node (ref "U4") (pin "21") (pinfunction "NC10_21") (pintype "passive+no_connect"))
    )
    (net (code "61") (name "unconnected-(U4-NC11-Pad22)") (class "Default")
      (node (ref "U4") (pin "22") (pinfunction "NC11_22") (pintype "passive+no_connect"))
    )
    (net (code "62") (name "unconnected-(U4-NC12-Pad23)") (class "Default")
      (node (ref "U4") (pin "23") (pinfunction "NC12_23") (pintype "passive+no_connect"))
    )
    (net (code "63") (name "unconnected-(U4-RI-Pad2)") (class "Default")
      (node (ref "U4") (pin "2") (pinfunction "RI_2") (pintype "passive+no_connect"))
    )
    (net (code "64") (name "unconnected-(U4-RST#-Pad9)") (class "Default")
      (node (ref "U4") (pin "9") (pinfunction "RST#_9") (pintype "passive+no_connect"))
    )
    (net (code "65") (name "unconnected-(U4-RTS-Pad24)") (class "Default")
      (node (ref "U4") (pin "24") (pinfunction "RTS_24") (pintype "passive+no_connect"))
    )
    (net (code "66") (name "unconnected-(U4-SUSPEND#-Pad11)") (class "Default")
      (node (ref "U4") (pin "11") (pinfunction "SUSPEND#_11") (pintype "passive+no_connect"))
    )
    (net (code "67") (name "unconnected-(U4-SUSPEND-Pad12)") (class "Default")
      (node (ref "U4") (pin "12") (pinfunction "SUSPEND_12") (pintype "passive+no_connect"))
    )
  )
)
